# RX.net
KiCad netlist of a schematic drawn in Altium Designer
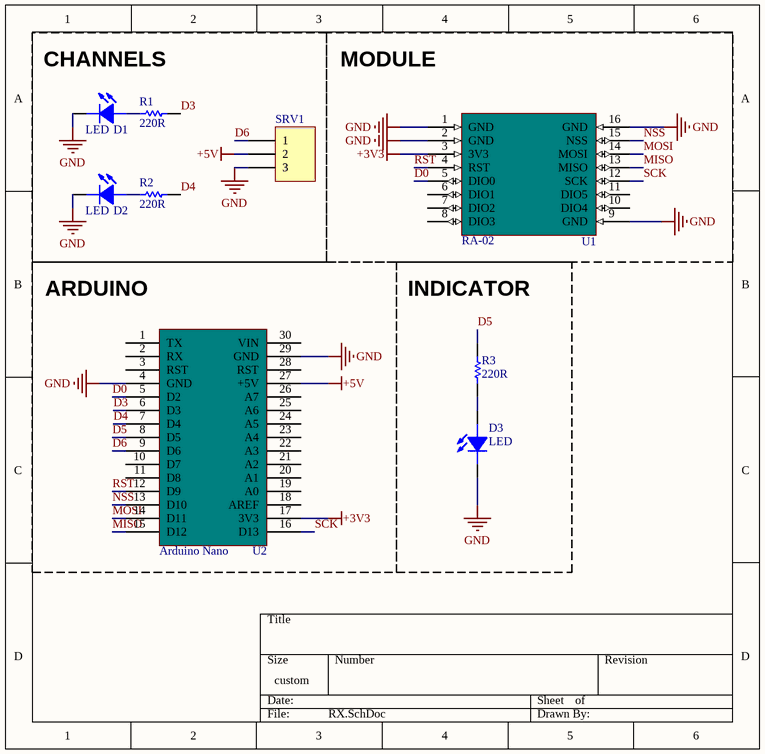
[diagram p0: RX.SchDoc]

(export (version "E")
  (design (tool "Eeschema 10.0.6"))
  (components
    (comp (ref "D1")
      (value "LED")
      (footprint "LED3mm_GRN")
      (description "Light Emitting Diode")
      (fields (field (name "DESIGNER") "Ali Hafizi"))
      (libsource (lib "Altium") (part "LED 3MM"))
    )
    (comp (ref "D2")
      (value "LED")
      (footprint "LED3mm_GRN")
      (description "Light Emitting Diode")
      (fields (field (name "DESIGNER") "Ali Hafizi"))
      (libsource (lib "Altium") (part "LED 3MM"))
    )
    (comp (ref "D3")
      (value "LED")
      (footprint "LED3mm_GRN")
      (description "Light Emitting Diode")
      (fields (field (name "DESIGNER") "Ali Hafizi"))
      (libsource (lib "Altium") (part "LED 3MM"))
    )
    (comp (ref "R1")
      (value "220R")
      (footprint "RES-(1/4)")
      (description "TOTAL DIP RESISTOR PACK")
      (fields (field (name "DESIGNER") "Ali Hafizi"))
      (libsource (lib "Altium") (part "RES DIP PACKAGE"))
    )
    (comp (ref "R2")
      (value "220R")
      (footprint "RES-(1/4)")
      (description "TOTAL DIP RESISTOR PACK")
      (fields (field (name "DESIGNER") "Ali Hafizi"))
      (libsource (lib "Altium") (part "RES DIP PACKAGE"))
    )
    (comp (ref "R3")
      (value "220R")
      (footprint "RES-(1/4)")
      (description "TOTAL DIP RESISTOR PACK")
      (fields (field (name "DESIGNER") "Ali Hafizi"))
      (libsource (lib "Altium") (part "RES DIP PACKAGE"))
    )
    (comp (ref "SRV1")
      (value "Header 3")
      (footprint "HDR1X3")
      (description "Header, 3-Pin")
      (fields (field (name "PUBLISHER") "Altium Limited"))
      (libsource (lib "Altium") (part "Header 3"))
    )
    (comp (ref "U1") (value "RA-02") (footprint "RA-02") (libsource (lib "LoRa-Ardino-Test") (part "RA-02")))
    (comp (ref "U2")
      (value "Arduino Nano")
      (footprint "Arduino_Nano328")
      (description "Arduino Nano 328")
      (libsource (lib "LoRa-Ardino-Test") (part "Arduino Nano"))
    )
  )
  (nets
    (net (code "1") (name "+3V3") (class "Default")
      (node (ref "U1") (pin "3") (pinfunction "3V3_3") (pintype "input"))
      (node (ref "U2") (pin "17") (pinfunction "3V3_17") (pintype "passive"))
    )
    (net (code "2") (name "+5V") (class "Default")
      (node (ref "SRV1") (pin "2") (pinfunction "2_2") (pintype "passive"))
      (node (ref "U2") (pin "27") (pinfunction "+5V_27") (pintype "passive"))
    )
    (net (code "3") (name "/D0") (class "Default")
      (node (ref "U1") (pin "5") (pinfunction "DIO0_5") (pintype "bidirectional"))
      (node (ref "U2") (pin "5") (pinfunction "D2_5") (pintype "passive"))
    )
    (net (code "4") (name "/D3") (class "Default")
      (node (ref "R1") (pin "2") (pinfunction "2_2") (pintype "passive"))
      (node (ref "U2") (pin "6") (pinfunction "D3_6") (pintype "passive"))
    )
    (net (code "5") (name "/D4") (class "Default")
      (node (ref "R2") (pin "2") (pinfunction "2_2") (pintype "passive"))
      (node (ref "U2") (pin "7") (pinfunction "D4_7") (pintype "passive"))
    )
    (net (code "6") (name "/D5") (class "Default")
      (node (ref "R3") (pin "2") (pinfunction "2_2") (pintype "passive"))
      (node (ref "U2") (pin "8") (pinfunction "D5_8") (pintype "passive"))
    )
    (net (code "7") (name "/D6") (class "Default")
      (node (ref "SRV1") (pin "1") (pinfunction "1_1") (pintype "passive"))
      (node (ref "U2") (pin "9") (pinfunction "D6_9") (pintype "passive"))
    )
    (net (code "8") (name "/MISO") (class "Default")
      (node (ref "U1") (pin "13") (pinfunction "MISO_13") (pintype "bidirectional"))
      (node (ref "U2") (pin "15") (pinfunction "D12_15") (pintype "passive"))
    )
    (net (code "9") (name "/MOSI") (class "Default")
      (node (ref "U1") (pin "14") (pinfunction "MOSI_14") (pintype "bidirectional"))
      (node (ref "U2") (pin "14") (pinfunction "D11_14") (pintype "passive"))
    )
    (net (code "10") (name "/NSS") (class "Default")
      (node (ref "U1") (pin "15") (pinfunction "NSS_15") (pintype "bidirectional"))
      (node (ref "U2") (pin "13") (pinfunction "D10_13") (pintype "passive"))
    )
    (net (code "11") (name "/RST") (class "Default")
      (node (ref "U1") (pin "4") (pinfunction "RST_4") (pintype "input"))
      (node (ref "U2") (pin "12") (pinfunction "D9_12") (pintype "passive"))
    )
    (net (code "12") (name "/SCK") (class "Default")
      (node (ref "U1") (pin "12") (pinfunction "SCK_12") (pintype "bidirectional"))
      (node (ref "U2") (pin "16") (pinfunction "D13_16") (pintype "passive"))
    )
    (net (code "13") (name "GND") (class "Default")
      (node (ref "D1") (pin "2") (pinfunction "CATHODE_2") (pintype "passive"))
      (node (ref "D2") (pin "2") (pinfunction "CATHODE_2") (pintype "passive"))
      (node (ref "D3") (pin "2") (pinfunction "CATHODE_2") (pintype "passive"))
      (node (ref "SRV1") (pin "3") (pinfunction "3_3") (pintype "passive"))
      (node (ref "U1") (pin "1") (pinfunction "GND_1") (pintype "input"))
      (node (ref "U1") (pin "16") (pinfunction "GND_16") (pintype "input"))
      (node (ref "U1") (pin "2") (pinfunction "GND_2") (pintype "input"))
      (node (ref "U1") (pin "9") (pinfunction "GND_9") (pintype "input"))
      (node (ref "U2") (pin "29") (pinfunction "GND_29") (pintype "passive"))
      (node (ref "U2") (pin "4") (pinfunction "GND_4") (pintype "passive"))
    )
    (net (code "14") (name "Net-(D1-ANODE)") (class "Default")
      (node (ref "D1") (pin "1") (pinfunction "ANODE_1") (pintype "passive"))
      (node (ref "R1") (pin "1") (pinfunction "1_1") (pintype "passive"))
    )
    (net (code "15") (name "Net-(D2-ANODE)") (class "Default")
      (node (ref "D2") (pin "1") (pinfunction "ANODE_1") (pintype "passive"))
      (node (ref "R2") (pin "1") (pinfunction "1_1") (pintype "passive"))
    )
    (net (code "16") (name "Net-(D3-ANODE)") (class "Default")
      (node (ref "D3") (pin "1") (pinfunction "ANODE_1") (pintype "passive"))
      (node (ref "R3") (pin "1") (pinfunction "1_1") (pintype "passive"))
    )
    (net (code "17") (name "unconnected-(U1-DIO1-Pad6)") (class "Default")
      (node (ref "U1") (pin "6") (pinfunction "DIO1_6") (pintype "bidirectional"))
    )
    (net (code "18") (name "unconnected-(U1-DIO2-Pad7)") (class "Default")
      (node (ref "U1") (pin "7") (pinfunction "DIO2_7") (pintype "bidirectional"))
    )
    (net (code "19") (name "unconnected-(U1-DIO3-Pad8)") (class "Default")
      (node (ref "U1") (pin "8") (pinfunction "DIO3_8") (pintype "bidirectional"))
    )
    (net (code "20") (name "unconnected-(U1-DIO4-Pad10)") (class "Default")
      (node (ref "U1") (pin "10") (pinfunction "DIO4_10") (pintype "bidirectional"))
    )
    (net (code "21") (name "unconnected-(U1-DIO5-Pad11)") (class "Default")
      (node (ref "U1") (pin "11") (pinfunction "DIO5_11") (pintype "bidirectional"))
    )
    (net (code "22") (name "unconnected-(U2-A0-Pad19)") (class "Default")
      (node (ref "U2") (pin "19") (pinfunction "A0_19") (pintype "passive"))
    )
    (net (code "23") (name "unconnected-(U2-A1-Pad20)") (class "Default")
      (node (ref "U2") (pin "20") (pinfunction "A1_20") (pintype "passive"))
    )
    (net (code "24") (name "unconnected-(U2-A2-Pad21)") (class "Default")
      (node (ref "U2") (pin "21") (pinfunction "A2_21") (pintype "passive"))
    )
    (net (code "25") (name "unconnected-(U2-A3-Pad22)") (class "Default")
      (node (ref "U2") (pin "22") (pinfunction "A3_22") (pintype "passive"))
    )
    (net (code "26") (name "unconnected-(U2-A4-Pad23)") (class "Default")
      (node (ref "U2") (pin "23") (pinfunction "A4_23") (pintype "passive"))
    )
    (net (code "27") (name "unconnected-(U2-A5-Pad24)") (class "Default")
      (node (ref "U2") (pin "24") (pinfunction "A5_24") (pintype "passive"))
    )
    (net (code "28") (name "unconnected-(U2-A6-Pad25)") (class "Default")
      (node (ref "U2") (pin "25") (pinfunction "A6_25") (pintype "passive"))
    )
    (net (code "29") (name "unconnected-(U2-A7-Pad26)") (class "Default")
      (node (ref "U2") (pin "26") (pinfunction "A7_26") (pintype "passive"))
    )
    (net (code "30") (name "unconnected-(U2-AREF-Pad18)") (class "Default")
      (node (ref "U2") (pin "18") (pinfunction "AREF_18") (pintype "passive"))
    )
    (net (code "31") (name "unconnected-(U2-D7-Pad10)") (class "Default")
      (node (ref "U2") (pin "10") (pinfunction "D7_10") (pintype "passive"))
    )
    (net (code "32") (name "unconnected-(U2-D8-Pad11)") (class "Default")
      (node (ref "U2") (pin "11") (pinfunction "D8_11") (pintype "passive"))
    )
    (net (code "33") (name "unconnected-(U2-RST-Pad3)") (class "Default")
      (node (ref "U2") (pin "3") (pinfunction "RST_3") (pintype "passive"))
    )
    (net (code "34") (name "unconnected-(U2-RST-Pad28)") (class "Default")
      (node (ref "U2") (pin "28") (pinfunction "RST_28") (pintype "passive"))
    )
    (net (code "35") (name "unconnected-(U2-RX-Pad2)") (class "Default")
      (node (ref "U2") (pin "2") (pinfunction "RX_2") (pintype "passive"))
    )
    (net (code "36") (name "unconnected-(U2-TX-Pad1)") (class "Default")
      (node (ref "U2") (pin "1") (pinfunction "TX_1") (pintype "passive"))
    )
    (net (code "37") (name "unconnected-(U2-VIN-Pad30)") (class "Default")
      (node (ref "U2") (pin "30") (pinfunction "VIN_30") (pintype "passive"))
    )
  )
)
